# TPSM82822_2A_3_8V_Buck_Module.net
KiCad netlist of a schematic drawn in Altium Designer
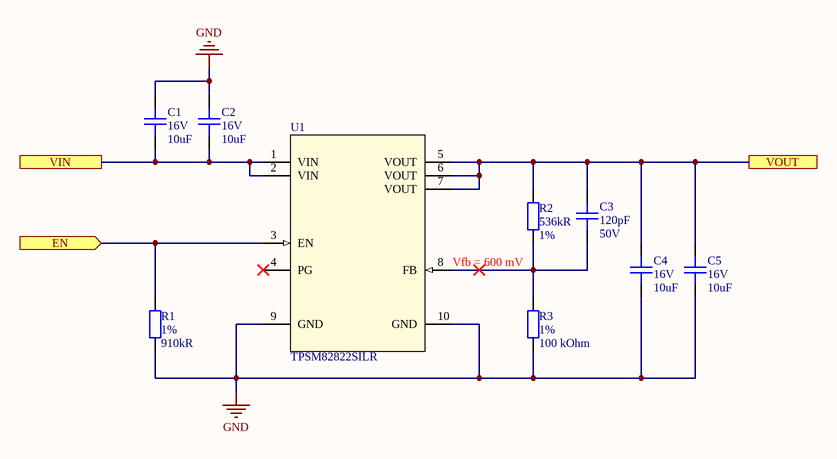
[diagram p0: TPSM82822_2A_3.8V_Buck_Module.SchDoc]

(export (version "E")
  (design (tool "Eeschema 10.0.6"))
  (components
    (comp (ref "C1")
      (value "CAP CER 10UF 16V X5R 0603")
      (footprint "C0603")
      (description "10µF ±10% 16V Ceramic Capacitor X5R 0603 (1608 Metric)")
      (fields
        (field (name "MANUFACTURER") "Murata")
        (field (name "MANUFACTURER PART NUMBER") "GRM188R61C106KAALJ")
        (field (name "VOLTAGE RATING") "16V")
        (field (name "CAPACITANCE") "10uF")
      )
      (libsource (lib "Control_Board_Model") (part "CAP CER 10UF 16V X5R 0603"))
    )
    (comp (ref "C2")
      (value "CAP CER 10UF 16V X5R 0603")
      (footprint "C0603")
      (description "10µF ±10% 16V Ceramic Capacitor X5R 0603 (1608 Metric)")
      (fields
        (field (name "MANUFACTURER") "Murata")
        (field (name "MANUFACTURER PART NUMBER") "GRM188R61C106KAALJ")
        (field (name "VOLTAGE RATING") "16V")
        (field (name "CAPACITANCE") "10uF")
      )
      (libsource (lib "Control_Board_Model") (part "CAP CER 10UF 16V X5R 0603"))
    )
    (comp (ref "C3")
      (value "CAP CER 120PF 50V C0G/NPO 0402")
      (footprint "C0402")
      (description "120pF ±5% 50V Ceramic Capacitor C0G, NP0 0402 (1005 Metric)")
      (fields
        (field (name "MANUFACTURER") "Yageo")
        (field (name "MANUFACTURER PART NUMBER") "CC0402JRNPO9BN121")
        (field (name "CAPACITANCE") "120pF")
        (field (name "VOLTAGE") "50V")
      )
      (libsource (lib "Control_Board_Model") (part "CAP CER 120PF 50V C0G/NPO 0402"))
    )
    (comp (ref "C4")
      (value "CAP CER 10UF 16V X5R 0603")
      (footprint "C0603")
      (description "10µF ±10% 16V Ceramic Capacitor X5R 0603 (1608 Metric)")
      (fields
        (field (name "MANUFACTURER") "Murata")
        (field (name "MANUFACTURER PART NUMBER") "GRM188R61C106KAALJ")
        (field (name "VOLTAGE RATING") "16V")
        (field (name "CAPACITANCE") "10uF")
      )
      (libsource (lib "Control_Board_Model") (part "CAP CER 10UF 16V X5R 0603"))
    )
    (comp (ref "C5")
      (value "CAP CER 10UF 16V X5R 0603")
      (footprint "C0603")
      (description "10µF ±10% 16V Ceramic Capacitor X5R 0603 (1608 Metric)")
      (fields
        (field (name "MANUFACTURER") "Murata")
        (field (name "MANUFACTURER PART NUMBER") "GRM188R61C106KAALJ")
        (field (name "VOLTAGE RATING") "16V")
        (field (name "CAPACITANCE") "10uF")
      )
      (libsource (lib "Control_Board_Model") (part "CAP CER 10UF 16V X5R 0603"))
    )
    (comp (ref "R1")
      (value "RES SMD 910K OHM 1% 1/16W 0402")
      (footprint "R0402")
      (description "910 kOhms ±1% 0.063W, 1/16W Chip Resistor 0402 (1005 Metric) Moisture Resistant Thick Film")
      (fields
        (field (name "MANUFACTURER") "Yageo")
        (field (name "MANUFACTURER PART NUMBER") "RC0402FR-07910KL")
        (field (name "TOLERANCE") "1%")
        (field (name "RESISTANCE") "910kR")
      )
      (libsource (lib "Control_Board_Model") (part "RES SMD 910K OHM 1% 1/16W 0402"))
    )
    (comp (ref "R2")
      (value "RES SMD 536K OHM 1% 1/16W 0402")
      (footprint "R0402")
      (description "536 kOhms ±1% 0.063W, 1/16W Chip Resistor 0402 (1005 Metric) Moisture Resistant Thick Film")
      (fields
        (field (name "MANUFACTURER") "Yageo")
        (field (name "MANUFACTURER PART NUMBER") "RC0402FR-07536KL")
        (field (name "RESISTANCE") "536kR")
        (field (name "TOLERANCE") "1%")
      )
      (libsource (lib "Control_Board_Model") (part "RES SMD 536K OHM 1% 1/16W 0402"))
    )
    (comp (ref "R3")
      (value "RES SMD 100K OHM 1% 1/16W 0402")
      (footprint "R0402")
      (description "100 kOhms ±1% 0.063W, 1/16W Chip Resistor 0402 (1005 Metric) Moisture Resistant Thick Film")
      (fields
        (field (name "MANUFACTURER") "Yageo")
        (field (name "MANUFACTURER PART NUMBER") "RC0402FR-07100KL")
        (field (name "TOLERANCE") "1%")
        (field (name "RESISTANCE") "100 kOhm")
      )
      (libsource (lib "Control_Board_Model") (part "RES SMD 100K OHM 1% 1/16W 0402"))
    )
    (comp (ref "U1")
      (value "TPSM82822SILR")
      (footprint "SIL0010D")
      (description "Non-Isolated PoL Module DC DC Converter 1 Output 0.6 ~ 4V    2A 2.4V - 5.5V Input")
      (fields (field (name "MANUFACTURER") "Texas Instruments"))
      (libsource (lib "dcdc_converters") (part "IC TPSM82822SIL 5.5-V INPUT, 2-A STEP-DOWN MODUL"))
    )
  )
  (nets
    (net (code "1") (name "/EN") (class "Default")
      (node (ref "R1") (pin "1") (pinfunction "1_1") (pintype "passive"))
      (node (ref "U1") (pin "3") (pinfunction "EN_3") (pintype "input"))
    )
    (net (code "2") (name "/VIN") (class "Default")
      (node (ref "C1") (pin "1") (pinfunction "1_1") (pintype "passive"))
      (node (ref "C2") (pin "1") (pinfunction "1_1") (pintype "passive"))
      (node (ref "U1") (pin "1") (pinfunction "VIN_1") (pintype "power_in"))
      (node (ref "U1") (pin "2") (pinfunction "VIN_2") (pintype "power_in"))
    )
    (net (code "3") (name "/VOUT") (class "Default")
      (node (ref "C3") (pin "2") (pinfunction "2_2") (pintype "passive"))
      (node (ref "C4") (pin "2") (pinfunction "2_2") (pintype "passive"))
      (node (ref "C5") (pin "2") (pinfunction "2_2") (pintype "passive"))
      (node (ref "R2") (pin "2") (pinfunction "2_2") (pintype "passive"))
      (node (ref "U1") (pin "5") (pinfunction "VOUT_5") (pintype "power_in"))
      (node (ref "U1") (pin "6") (pinfunction "VOUT_6") (pintype "power_in"))
      (node (ref "U1") (pin "7") (pinfunction "VOUT_7") (pintype "power_in"))
    )
    (net (code "4") (name "GND") (class "Default")
      (node (ref "C1") (pin "2") (pinfunction "2_2") (pintype "passive"))
      (node (ref "C2") (pin "2") (pinfunction "2_2") (pintype "passive"))
      (node (ref "C4") (pin "1") (pinfunction "1_1") (pintype "passive"))
      (node (ref "C5") (pin "1") (pinfunction "1_1") (pintype "passive"))
      (node (ref "R1") (pin "2") (pinfunction "2_2") (pintype "passive"))
      (node (ref "R3") (pin "1") (pinfunction "1_1") (pintype "passive"))
      (node (ref "U1") (pin "10") (pinfunction "GND_10") (pintype "power_in"))
      (node (ref "U1") (pin "9") (pinfunction "GND_9") (pintype "power_in"))
    )
    (net (code "5") (name "Net-(U1-FB)") (class "Default")
      (node (ref "C3") (pin "1") (pinfunction "1_1") (pintype "passive"))
      (node (ref "R2") (pin "1") (pinfunction "1_1") (pintype "passive"))
      (node (ref "R3") (pin "2") (pinfunction "2_2") (pintype "passive"))
      (node (ref "U1") (pin "8") (pinfunction "FB_8") (pintype "input"))
    )
    (net (code "6") (name "unconnected-(U1-PG-Pad4)") (class "Default")
      (node (ref "U1") (pin "4") (pinfunction "PG_4") (pintype "open_collector+no_connect"))
    )
  )
)
